# MX1508.net
KiCad netlist of a schematic drawn in Altium Designer
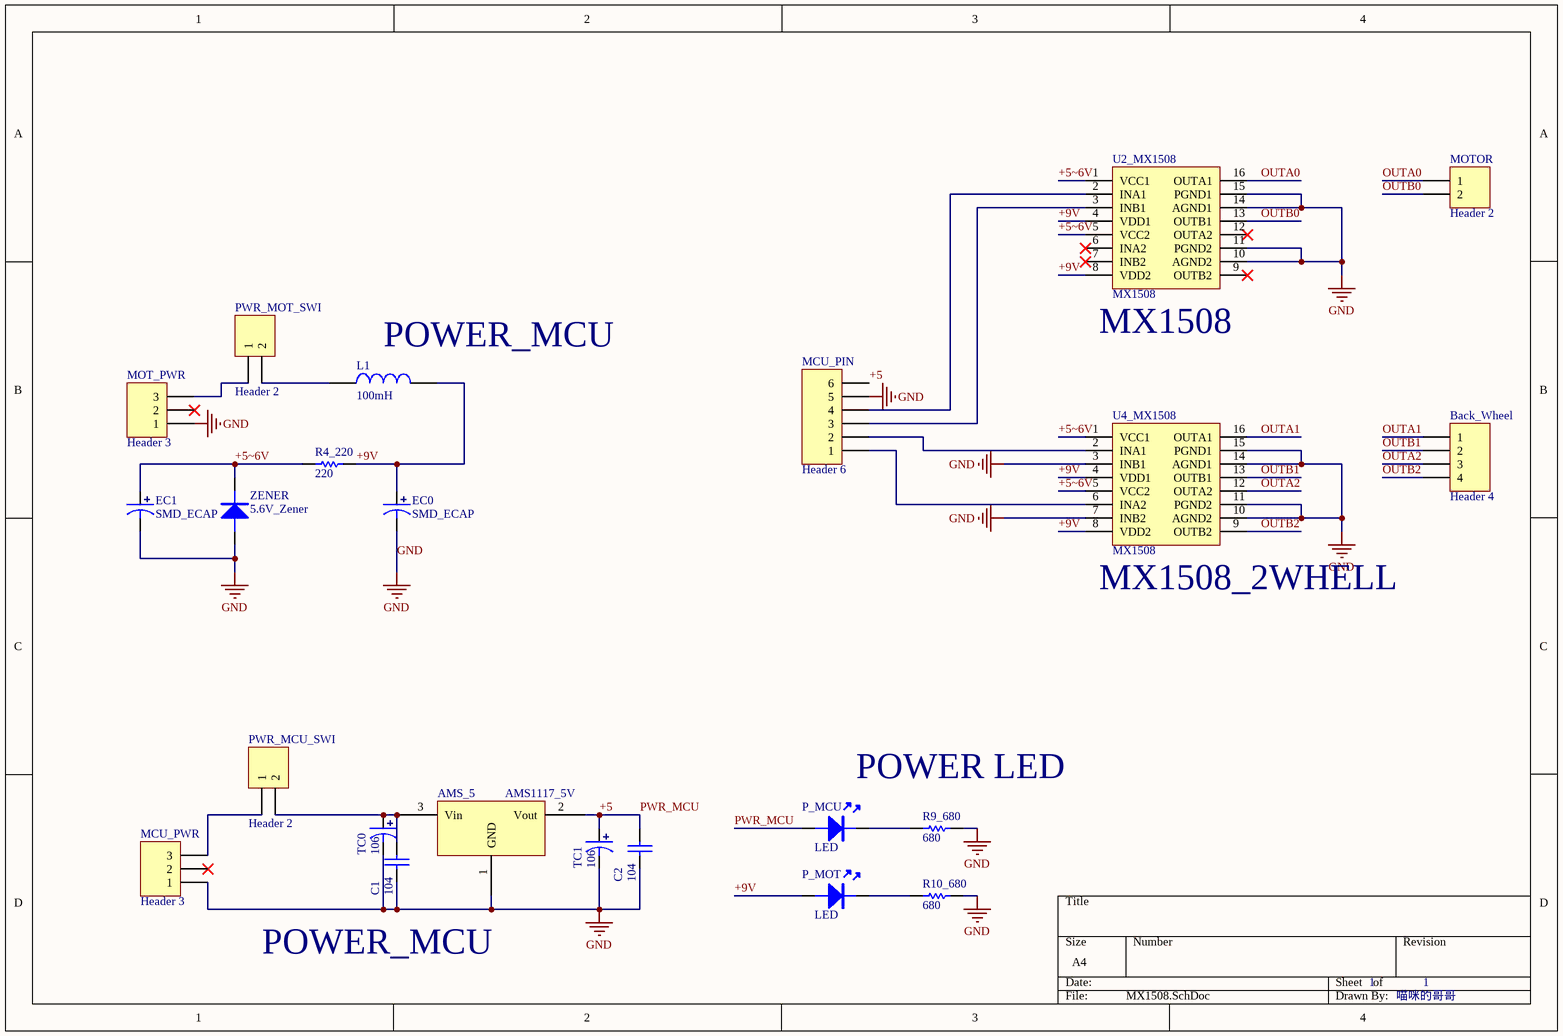
[diagram p0: MX1508.SchDoc]

(export (version "E")
  (design (tool "Eeschema 10.0.6"))
  (components
    (comp (ref "AMS_5")
      (value "AMS1117_5V")
      (footprint "SOT223")
      (description "三端稳压芯片")
      (libsource (lib "电源芯片") (part "AMS1117"))
    )
    (comp (ref "Back_Wheel")
      (value "Header 4")
      (footprint "HDR1X4")
      (description "Header, 4-Pin")
      (fields (field (name "PUBLISHER") "Altium Limited"))
      (libsource (lib "Miscellaneous Connectors") (part "Header 4"))
    )
    (comp (ref "C1")
      (value "104")
      (footprint "0402C")
      (description "无极性电容")
      (libsource (lib "电容") (part "CAP"))
    )
    (comp (ref "C2")
      (value "104")
      (footprint "0402C")
      (description "无极性电容")
      (libsource (lib "电容") (part "CAP"))
    )
    (comp (ref "EC0")
      (value "SMD_ECAP")
      (footprint "SMD-EC6.3X6.3X10")
      (description "贴片电解电容")
      (libsource (lib "电容") (part "SMD_ECAP"))
    )
    (comp (ref "EC1")
      (value "SMD_ECAP")
      (footprint "SMD-EC6.3X6.3X10")
      (description "贴片电解电容")
      (libsource (lib "电容") (part "SMD_ECAP"))
    )
    (comp (ref "L1")
      (value "100mH")
      (footprint "0603L")
      (description "INDUCTOR")
      (libsource (lib "电感") (part "INDUCTOR"))
    )
    (comp (ref "MCU_PIN")
      (value "Header 6")
      (footprint "HDR1X6")
      (description "Header, 6-Pin")
      (fields (field (name "PUBLISHER") "Altium Limited"))
      (libsource (lib "Miscellaneous Connectors") (part "Header 6"))
    )
    (comp (ref "MCU_PWR")
      (value "Header 3")
      (footprint "HDR1X3")
      (description "Header, 3-Pin")
      (fields (field (name "PUBLISHER") "Altium Limited"))
      (libsource (lib "Miscellaneous Connectors") (part "Header 3"))
    )
    (comp (ref "MOTOR")
      (value "Header 2")
      (footprint "HDR1X2")
      (description "Header, 2-Pin")
      (fields (field (name "PUBLISHER") "Altium Limited"))
      (libsource (lib "") (part "Header 2_1"))
    )
    (comp (ref "MOT_PWR")
      (value "Header 3")
      (footprint "HDR1X3")
      (description "Header, 3-Pin")
      (fields (field (name "PUBLISHER") "Altium Limited"))
      (libsource (lib "Miscellaneous Connectors") (part "Header 3"))
    )
    (comp (ref "PWR_MCU_SWI")
      (value "Header 2")
      (footprint "HDR1X2")
      (description "Header, 2-Pin")
      (fields (field (name "PUBLISHER") "Altium Limited"))
      (libsource (lib "Miscellaneous Connectors") (part "Header 2"))
    )
    (comp (ref "PWR_MOT_SWI")
      (value "Header 2")
      (footprint "HDR1X2")
      (description "Header, 2-Pin")
      (fields (field (name "PUBLISHER") "Altium Limited"))
      (libsource (lib "Miscellaneous Connectors") (part "Header 2"))
    )
    (comp (ref "P_MCU") (value "LED") (footprint "LED-0603Y") (libsource (lib "LED") (part "LED")))
    (comp (ref "P_MOT") (value "LED") (footprint "LED-0603Y") (libsource (lib "LED") (part "LED")))
    (comp (ref "R4_220") (value "220") (footprint "0402R") (libsource (lib "电阻") (part "RES")))
    (comp (ref "R9_680") (value "680") (footprint "0402R") (libsource (lib "电阻") (part "RES")))
    (comp (ref "R10_680") (value "680") (footprint "0402R") (libsource (lib "电阻") (part "RES")))
    (comp (ref "TC0")
      (value "106")
      (footprint "TAJ-A/3216")
      (description "钽电容")
      (libsource (lib "电容") (part "TCAP"))
    )
    (comp (ref "TC1")
      (value "106")
      (footprint "TAJ-A/3216")
      (description "钽电容")
      (libsource (lib "电容") (part "TCAP"))
    )
    (comp (ref "U2_MX1508") (value "MX1508") (footprint "SOP16") (libsource (lib "未分类IC") (part "MX1508")))
    (comp (ref "U4_MX1508") (value "MX1508") (footprint "SOP16") (libsource (lib "未分类IC") (part "MX1508")))
    (comp (ref "ZENER")
      (value "5.6V_Zener")
      (footprint "LL34")
      (description "普通二极管")
      (libsource (lib "二极管") (part "DIODE"))
    )
  )
  (nets
    (net (code "1") (name "/+5") (class "Default")
      (node (ref "AMS_5") (pin "2") (pinfunction "Vout_2") (pintype "passive"))
      (node (ref "C2") (pin "2") (pinfunction "2_2") (pintype "passive"))
      (node (ref "MCU_PIN") (pin "6") (pinfunction "6_6") (pintype "passive"))
      (node (ref "P_MCU") (pin "A") (pinfunction "A_A") (pintype "passive"))
      (node (ref "TC1") (pin "1") (pinfunction "1_1") (pintype "passive"))
    )
    (net (code "2") (name "/+5~6V") (class "Default")
      (node (ref "EC1") (pin "1") (pinfunction "1_1") (pintype "passive"))
      (node (ref "R4_220") (pin "1") (pinfunction "1_1") (pintype "passive"))
      (node (ref "U2_MX1508") (pin "1") (pinfunction "VCC1_1") (pintype "passive"))
      (node (ref "U2_MX1508") (pin "5") (pinfunction "VCC2_5") (pintype "passive"))
      (node (ref "U4_MX1508") (pin "1") (pinfunction "VCC1_1") (pintype "passive"))
      (node (ref "U4_MX1508") (pin "5") (pinfunction "VCC2_5") (pintype "passive"))
      (node (ref "ZENER") (pin "K") (pinfunction "K_K") (pintype "passive"))
    )
    (net (code "3") (name "/+9V") (class "Default")
      (node (ref "EC0") (pin "1") (pinfunction "1_1") (pintype "passive"))
      (node (ref "L1") (pin "2") (pinfunction "2_2") (pintype "passive"))
      (node (ref "P_MOT") (pin "A") (pinfunction "A_A") (pintype "passive"))
      (node (ref "R4_220") (pin "2") (pinfunction "2_2") (pintype "passive"))
      (node (ref "U2_MX1508") (pin "4") (pinfunction "VDD1_4") (pintype "passive"))
      (node (ref "U2_MX1508") (pin "8") (pinfunction "VDD2_8") (pintype "passive"))
      (node (ref "U4_MX1508") (pin "4") (pinfunction "VDD1_4") (pintype "passive"))
      (node (ref "U4_MX1508") (pin "8") (pinfunction "VDD2_8") (pintype "passive"))
    )
    (net (code "4") (name "/OUTA0") (class "Default")
      (node (ref "MOTOR") (pin "1") (pinfunction "1_1") (pintype "passive"))
      (node (ref "U2_MX1508") (pin "16") (pinfunction "OUTA1_16") (pintype "passive"))
    )
    (net (code "5") (name "/OUTA1") (class "Default")
      (node (ref "Back_Wheel") (pin "1") (pinfunction "1_1") (pintype "passive"))
      (node (ref "U4_MX1508") (pin "16") (pinfunction "OUTA1_16") (pintype "passive"))
    )
    (net (code "6") (name "/OUTA2") (class "Default")
      (node (ref "Back_Wheel") (pin "3") (pinfunction "3_3") (pintype "passive"))
      (node (ref "U4_MX1508") (pin "12") (pinfunction "OUTA2_12") (pintype "passive"))
    )
    (net (code "7") (name "/OUTB0") (class "Default")
      (node (ref "MOTOR") (pin "2") (pinfunction "2_2") (pintype "passive"))
      (node (ref "U2_MX1508") (pin "13") (pinfunction "OUTB1_13") (pintype "passive"))
    )
    (net (code "8") (name "/OUTB1") (class "Default")
      (node (ref "Back_Wheel") (pin "2") (pinfunction "2_2") (pintype "passive"))
      (node (ref "U4_MX1508") (pin "13") (pinfunction "OUTB1_13") (pintype "passive"))
    )
    (net (code "9") (name "/OUTB2") (class "Default")
      (node (ref "Back_Wheel") (pin "4") (pinfunction "4_4") (pintype "passive"))
      (node (ref "U4_MX1508") (pin "9") (pinfunction "OUTB2_9") (pintype "passive"))
    )
    (net (code "10") (name "GND") (class "Default")
      (node (ref "AMS_5") (pin "1") (pinfunction "GND_1") (pintype "passive"))
      (node (ref "C1") (pin "1") (pinfunction "1_1") (pintype "passive"))
      (node (ref "C2") (pin "1") (pinfunction "1_1") (pintype "passive"))
      (node (ref "EC0") (pin "2") (pinfunction "2_2") (pintype "passive"))
      (node (ref "EC1") (pin "2") (pinfunction "2_2") (pintype "passive"))
      (node (ref "MCU_PIN") (pin "5") (pinfunction "5_5") (pintype "passive"))
      (node (ref "MCU_PWR") (pin "1") (pinfunction "1_1") (pintype "passive"))
      (node (ref "MOT_PWR") (pin "1") (pinfunction "1_1") (pintype "passive"))
      (node (ref "R10_680") (pin "1") (pinfunction "1_1") (pintype "passive"))
      (node (ref "R9_680") (pin "1") (pinfunction "1_1") (pintype "passive"))
      (node (ref "TC0") (pin "2") (pinfunction "2_2") (pintype "passive"))
      (node (ref "TC1") (pin "2") (pinfunction "2_2") (pintype "passive"))
      (node (ref "U2_MX1508") (pin "10") (pinfunction "AGND2_10") (pintype "passive"))
      (node (ref "U2_MX1508") (pin "11") (pinfunction "PGND2_11") (pintype "passive"))
      (node (ref "U2_MX1508") (pin "14") (pinfunction "AGND1_14") (pintype "passive"))
      (node (ref "U2_MX1508") (pin "15") (pinfunction "PGND1_15") (pintype "passive"))
      (node (ref "U4_MX1508") (pin "10") (pinfunction "AGND2_10") (pintype "passive"))
      (node (ref "U4_MX1508") (pin "11") (pinfunction "PGND2_11") (pintype "passive"))
      (node (ref "U4_MX1508") (pin "14") (pinfunction "AGND1_14") (pintype "passive"))
      (node (ref "U4_MX1508") (pin "15") (pinfunction "PGND1_15") (pintype "passive"))
      (node (ref "U4_MX1508") (pin "3") (pinfunction "INB1_3") (pintype "passive"))
      (node (ref "U4_MX1508") (pin "7") (pinfunction "INB2_7") (pintype "passive"))
      (node (ref "ZENER") (pin "A") (pinfunction "A_A") (pintype "passive"))
    )
    (net (code "11") (name "Net-(AMS_5-Vin)") (class "Default")
      (node (ref "AMS_5") (pin "3") (pinfunction "Vin_3") (pintype "passive"))
      (node (ref "C1") (pin "2") (pinfunction "2_2") (pintype "passive"))
      (node (ref "PWR_MCU_SWI") (pin "2") (pinfunction "2_2") (pintype "passive"))
      (node (ref "TC0") (pin "1") (pinfunction "1_1") (pintype "passive"))
    )
    (net (code "12") (name "Net-(L1-Pad1)") (class "Default")
      (node (ref "L1") (pin "1") (pinfunction "1_1") (pintype "passive"))
      (node (ref "PWR_MOT_SWI") (pin "2") (pinfunction "2_2") (pintype "passive"))
    )
    (net (code "13") (name "Net-(MCU_PWR-Pad3)") (class "Default")
      (node (ref "MCU_PWR") (pin "3") (pinfunction "3_3") (pintype "passive"))
      (node (ref "PWR_MCU_SWI") (pin "1") (pinfunction "1_1") (pintype "passive"))
    )
    (net (code "14") (name "Net-(MOT_PWR-Pad3)") (class "Default")
      (node (ref "MOT_PWR") (pin "3") (pinfunction "3_3") (pintype "passive"))
      (node (ref "PWR_MOT_SWI") (pin "1") (pinfunction "1_1") (pintype "passive"))
    )
    (net (code "15") (name "Net-(P_MCU-PadK)") (class "Default")
      (node (ref "P_MCU") (pin "K") (pinfunction "K_K") (pintype "passive"))
      (node (ref "R9_680") (pin "2") (pinfunction "2_2") (pintype "passive"))
    )
    (net (code "16") (name "Net-(P_MOT-PadK)") (class "Default")
      (node (ref "P_MOT") (pin "K") (pinfunction "K_K") (pintype "passive"))
      (node (ref "R10_680") (pin "2") (pinfunction "2_2") (pintype "passive"))
    )
    (net (code "17") (name "Net-(U2_MX1508-INA1)") (class "Default")
      (node (ref "MCU_PIN") (pin "4") (pinfunction "4_4") (pintype "passive"))
      (node (ref "U2_MX1508") (pin "2") (pinfunction "INA1_2") (pintype "passive"))
    )
    (net (code "18") (name "Net-(U2_MX1508-INB1)") (class "Default")
      (node (ref "MCU_PIN") (pin "3") (pinfunction "3_3") (pintype "passive"))
      (node (ref "U2_MX1508") (pin "3") (pinfunction "INB1_3") (pintype "passive"))
    )
    (net (code "19") (name "Net-(U4_MX1508-INA1)") (class "Default")
      (node (ref "MCU_PIN") (pin "2") (pinfunction "2_2") (pintype "passive"))
      (node (ref "U4_MX1508") (pin "2") (pinfunction "INA1_2") (pintype "passive"))
    )
    (net (code "20") (name "Net-(U4_MX1508-INA2)") (class "Default")
      (node (ref "MCU_PIN") (pin "1") (pinfunction "1_1") (pintype "passive"))
      (node (ref "U4_MX1508") (pin "6") (pinfunction "INA2_6") (pintype "passive"))
    )
    (net (code "21") (name "unconnected-(MCU_PWR-Pad2)") (class "Default")
      (node (ref "MCU_PWR") (pin "2") (pinfunction "2_2") (pintype "passive+no_connect"))
    )
    (net (code "22") (name "unconnected-(MOT_PWR-Pad2)") (class "Default")
      (node (ref "MOT_PWR") (pin "2") (pinfunction "2_2") (pintype "passive+no_connect"))
    )
    (net (code "23") (name "unconnected-(U2_MX1508-INA2-Pad6)") (class "Default")
      (node (ref "U2_MX1508") (pin "6") (pinfunction "INA2_6") (pintype "passive+no_connect"))
    )
    (net (code "24") (name "unconnected-(U2_MX1508-INB2-Pad7)") (class "Default")
      (node (ref "U2_MX1508") (pin "7") (pinfunction "INB2_7") (pintype "passive+no_connect"))
    )
    (net (code "25") (name "unconnected-(U2_MX1508-OUTA2-Pad12)") (class "Default")
      (node (ref "U2_MX1508") (pin "12") (pinfunction "OUTA2_12") (pintype "passive+no_connect"))
    )
    (net (code "26") (name "unconnected-(U2_MX1508-OUTB2-Pad9)") (class "Default")
      (node (ref "U2_MX1508") (pin "9") (pinfunction "OUTB2_9") (pintype "passive+no_connect"))
    )
  )
)
